# Power.net
KiCad netlist of a schematic drawn in Altium Designer
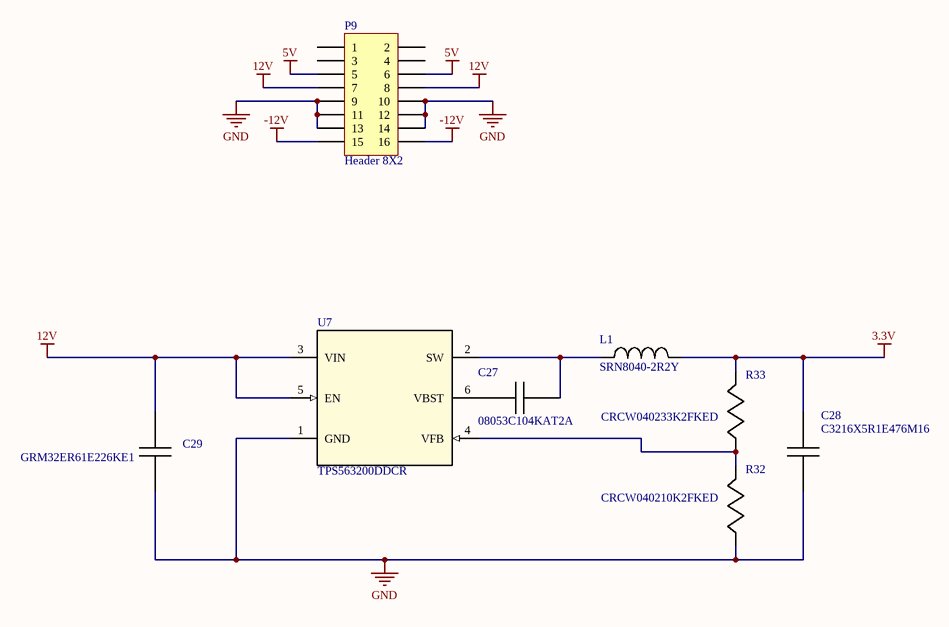
[diagram p0: Power.SchDoc]

(export (version "E")
  (design (tool "Eeschema 10.0.6"))
  (components
    (comp (ref "C27")
      (value "08053C104KAT2A")
      (footprint "0805")
      (description "Imported")
      (libsource (lib "2017-10-30_10-27-00") (part "08053C104KAT2A"))
    )
    (comp (ref "C28")
      (value "C3216X5R1E476M16")
      (footprint "1206")
      (description "Imported")
      (fields (field (name "MANUFACTURER_PART_NUMBER") "C3216X5R1E476M160AC"))
      (libsource (lib "2017-10-30_10-27-00") (part "C3216X5R1E476M16"))
    )
    (comp (ref "C29")
      (value "GRM32ER61E226KE1")
      (footprint "1210")
      (description "Imported")
      (fields (field (name "MANUFACTURER_PART_NUMBER") "GRM32ER61E226KE15L"))
      (libsource (lib "2017-10-30_10-27-00") (part "GRM32ER61E226KE1"))
    )
    (comp (ref "L1")
      (value "SRN8040-2R2Y")
      (footprint "SRN8040")
      (description "Imported")
      (libsource (lib "2017-10-03_20-29-25") (part "SRN8040-2R2Y"))
    )
    (comp (ref "P9")
      (value "Header 8X2")
      (footprint "HDR2X8")
      (description "Header, 8-Pin, Dual row")
      (fields (field (name "PUBLISHER") "Altium Limited"))
      (libsource (lib "Miscellaneous Connectors") (part "Header 8X2"))
    )
    (comp (ref "R32")
      (value "CRCW040210K2FKED")
      (footprint "0402")
      (description "Imported")
      (libsource (lib "2017-10-30_10-27-00") (part "CRCW040210K2FKED"))
    )
    (comp (ref "R33")
      (value "CRCW040233K2FKED")
      (footprint "0402")
      (description "Imported")
      (libsource (lib "2017-10-30_10-27-00") (part "CRCW040233K2FKED"))
    )
    (comp (ref "U7")
      (value "TPS563200DDCR")
      (footprint "DDC0006A")
      (description "Imported")
      (fields
        (field (name "PARTNUMBER") "TPS563200DDC")
        (field (name "MANUFACTURER") "Texas Instruments")
        (field (name "MODIFIEDDATE") "Not shown in title block")
        (field (name "APPROVEDBY") "Not shown in title block")
        (field (name "CHECKEDBY") "Not shown in title block")
        (field (name "AUTHOR") "Not shown in title block")
        (field (name "ENGINEER") "Not shown in title block")
        (field (name "SYMBOLCREATOR") "a0411947")
        (field (name "PUBLISHER") "Texas Instruments")
      )
      (libsource (lib "2017-10-03_20-29-25") (part "TPS563200DDCR"))
    )
  )
  (nets
    (net (code "1") (name "-12V") (class "Default")
      (node (ref "P9") (pin "15") (pinfunction "15_15") (pintype "passive"))
      (node (ref "P9") (pin "16") (pinfunction "16_16") (pintype "passive"))
    )
    (net (code "2") (name "3.3V") (class "Default")
      (node (ref "C28") (pin "1") (pinfunction "1_1") (pintype "passive"))
      (node (ref "L1") (pin "2") (pinfunction "2_2") (pintype "passive"))
      (node (ref "R33") (pin "1") (pinfunction "1_1") (pintype "passive"))
    )
    (net (code "3") (name "5V") (class "Default")
      (node (ref "P9") (pin "5") (pinfunction "5_5") (pintype "passive"))
      (node (ref "P9") (pin "6") (pinfunction "6_6") (pintype "passive"))
    )
    (net (code "4") (name "12V") (class "Default")
      (node (ref "C29") (pin "1") (pinfunction "1_1") (pintype "passive"))
      (node (ref "P9") (pin "7") (pinfunction "7_7") (pintype "passive"))
      (node (ref "P9") (pin "8") (pinfunction "8_8") (pintype "passive"))
      (node (ref "U7") (pin "3") (pinfunction "VIN_3") (pintype "power_in"))
      (node (ref "U7") (pin "5") (pinfunction "EN_5") (pintype "input"))
    )
    (net (code "5") (name "GND") (class "Default")
      (node (ref "C28") (pin "2") (pinfunction "2_2") (pintype "passive"))
      (node (ref "C29") (pin "2") (pinfunction "2_2") (pintype "passive"))
      (node (ref "P9") (pin "10") (pinfunction "10_10") (pintype "passive"))
      (node (ref "P9") (pin "11") (pinfunction "11_11") (pintype "passive"))
      (node (ref "P9") (pin "12") (pinfunction "12_12") (pintype "passive"))
      (node (ref "P9") (pin "13") (pinfunction "13_13") (pintype "passive"))
      (node (ref "P9") (pin "14") (pinfunction "14_14") (pintype "passive"))
      (node (ref "P9") (pin "9") (pinfunction "9_9") (pintype "passive"))
      (node (ref "R32") (pin "2") (pinfunction "2_2") (pintype "passive"))
      (node (ref "U7") (pin "1") (pinfunction "GND_1") (pintype "power_in"))
    )
    (net (code "6") (name "Net-(U7-SW)") (class "Default")
      (node (ref "C27") (pin "1") (pinfunction "1_1") (pintype "passive"))
      (node (ref "L1") (pin "1") (pinfunction "1_1") (pintype "passive"))
      (node (ref "U7") (pin "2") (pinfunction "SW_2") (pintype "power_in"))
    )
    (net (code "7") (name "Net-(U7-VBST)") (class "Default")
      (node (ref "C27") (pin "2") (pinfunction "2_2") (pintype "passive"))
      (node (ref "U7") (pin "6") (pinfunction "VBST_6") (pintype "power_in"))
    )
    (net (code "8") (name "Net-(U7-VFB)") (class "Default")
      (node (ref "R32") (pin "1") (pinfunction "1_1") (pintype "passive"))
      (node (ref "R33") (pin "2") (pinfunction "2_2") (pintype "passive"))
      (node (ref "U7") (pin "4") (pinfunction "VFB_4") (pintype "input"))
    )
    (net (code "9") (name "unconnected-(P9-Pad1)") (class "Default")
      (node (ref "P9") (pin "1") (pinfunction "1_1") (pintype "passive"))
    )
    (net (code "10") (name "unconnected-(P9-Pad2)") (class "Default")
      (node (ref "P9") (pin "2") (pinfunction "2_2") (pintype "passive"))
    )
    (net (code "11") (name "unconnected-(P9-Pad3)") (class "Default")
      (node (ref "P9") (pin "3") (pinfunction "3_3") (pintype "passive"))
    )
    (net (code "12") (name "unconnected-(P9-Pad4)") (class "Default")
      (node (ref "P9") (pin "4") (pinfunction "4_4") (pintype "passive"))
    )
  )
)
